# initial_schematic.net
KiCad netlist of a schematic drawn in EAGLE
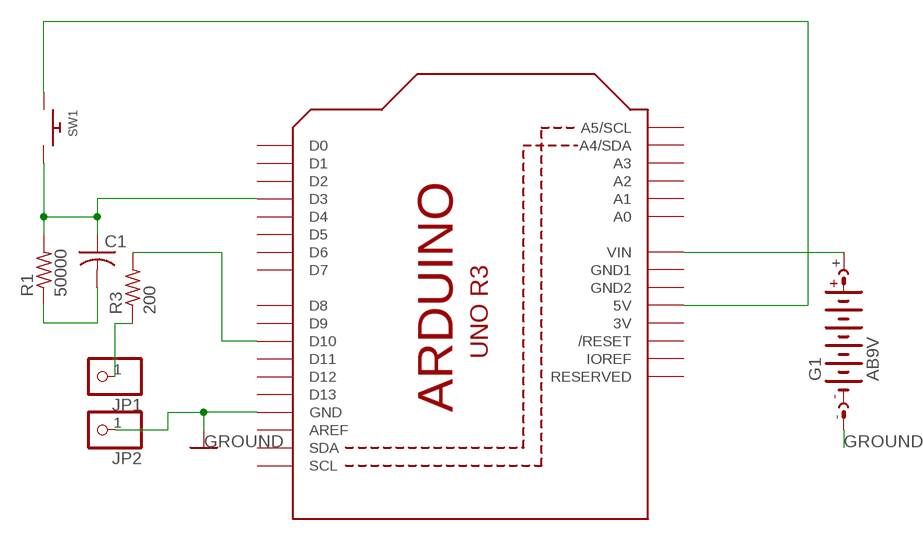
[diagram p0: schematic, sheet 1]

(export (version "E")
  (design (tool "Eeschema 10.0.6"))
  (components
    (comp (ref "C1")
      (value "C-USC0805")
      (footprint "eagle-import:C0805")
      (libsource (lib "eagle-import") (part "C-USC0805"))
    )
    (comp (ref "G1")
      (value "AB9V")
      (footprint "eagle-import:AB9V")
      (libsource (lib "eagle-import") (part "AB9V"))
    )
    (comp (ref "JP1")
      (value "PINHD-1X1")
      (footprint "eagle-import:1X01")
      (libsource (lib "eagle-import") (part "PINHD-1X1"))
    )
    (comp (ref "JP2")
      (value "PINHD-1X1")
      (footprint "eagle-import:1X01")
      (libsource (lib "eagle-import") (part "PINHD-1X1"))
    )
    (comp (ref "R1")
      (value "50000")
      (footprint "eagle-import:R0805W")
      (libsource (lib "eagle-import") (part "R-US_R0805W"))
    )
    (comp (ref "R3")
      (value "200")
      (footprint "eagle-import:R0805W")
      (libsource (lib "eagle-import") (part "R-US_R0805W"))
    )
    (comp (ref "SW1")
      (value "SWITCH_PUSHBUTTONC&K_KSS")
      (footprint "eagle-import:BTN_CK_KSS")
      (libsource (lib "eagle-import") (part "SWITCH_PUSHBUTTONC&K_KSS"))
    )
    (comp (ref "U1")
      (value "ARDUINOR3-DIMENSION")
      (footprint "eagle-import:ARDUINOR3")
      (libsource (lib "eagle-import") (part "ARDUINOR3-DIMENSION"))
    )
  )
  (nets
    (net (code "1") (name "/3V") (class "Default")
      (node (ref "U1") (pin "3V") (pinfunction "3V_3V") (pintype "power_in"))
    )
    (net (code "2") (name "/GND1") (class "Default")
      (node (ref "U1") (pin "GND1") (pinfunction "GND1_GND1") (pintype "power_in"))
    )
    (net (code "3") (name "/GND2") (class "Default")
      (node (ref "U1") (pin "GND2") (pinfunction "GND2_GND2") (pintype "power_in"))
    )
    (net (code "4") (name "GND") (class "Default")
      (node (ref "JP2") (pin "1") (pinfunction "1_1") (pintype "passive"))
      (node (ref "U1") (pin "GND") (pinfunction "GND_GND") (pintype "power_in"))
    )
    (net (code "5") (name "Net-(C1-Pad1)") (class "Default")
      (node (ref "C1") (pin "1") (pinfunction "1_1") (pintype "passive"))
      (node (ref "R1") (pin "2") (pinfunction "2_2") (pintype "passive"))
      (node (ref "SW1") (pin "P$2") (pinfunction "P$2_P$2") (pintype "passive"))
      (node (ref "U1") (pin "D3") (pinfunction "D3_D3") (pintype "bidirectional"))
    )
    (net (code "6") (name "Net-(C1-Pad2)") (class "Default")
      (node (ref "C1") (pin "2") (pinfunction "2_2") (pintype "passive"))
      (node (ref "R1") (pin "1") (pinfunction "1_1") (pintype "passive"))
    )
    (net (code "7") (name "Net-(G1-Pad+)") (class "Default")
      (node (ref "G1") (pin "+") (pinfunction "+_+") (pintype "passive"))
      (node (ref "U1") (pin "VIN") (pinfunction "VIN_VIN") (pintype "power_in"))
    )
    (net (code "8") (name "Net-(JP1-Pad1)") (class "Default")
      (node (ref "JP1") (pin "1") (pinfunction "1_1") (pintype "passive"))
      (node (ref "R3") (pin "1") (pinfunction "1_1") (pintype "passive"))
    )
    (net (code "9") (name "Net-(R3-Pad2)") (class "Default")
      (node (ref "R3") (pin "2") (pinfunction "2_2") (pintype "passive"))
      (node (ref "U1") (pin "D10") (pinfunction "D10_D10") (pintype "bidirectional"))
    )
    (net (code "10") (name "Net-(SW1-PadP$1)") (class "Default")
      (node (ref "SW1") (pin "P$1") (pinfunction "P$1_P$1") (pintype "passive"))
      (node (ref "U1") (pin "5V") (pinfunction "5V_5V") (pintype "power_in"))
    )
    (net (code "11") (name "unconnected-(G1-Pad-)") (class "Default")
      (node (ref "G1") (pin "-") (pinfunction "-_-") (pintype "passive"))
    )
    (net (code "12") (name "unconnected-(U1-A4{slash}SDA-PadA4)") (class "Default")
      (node (ref "U1") (pin "A4") (pinfunction "A4/SDA_A4") (pintype "bidirectional"))
    )
    (net (code "13") (name "unconnected-(U1-A5{slash}SCL-PadA5)") (class "Default")
      (node (ref "U1") (pin "A5") (pinfunction "A5/SCL_A5") (pintype "bidirectional"))
    )
    (net (code "14") (name "unconnected-(U1-PadA0)") (class "Default")
      (node (ref "U1") (pin "A0") (pinfunction "A0_A0") (pintype "bidirectional"))
    )
    (net (code "15") (name "unconnected-(U1-PadA1)") (class "Default")
      (node (ref "U1") (pin "A1") (pinfunction "A1_A1") (pintype "bidirectional"))
    )
    (net (code "16") (name "unconnected-(U1-PadA2)") (class "Default")
      (node (ref "U1") (pin "A2") (pinfunction "A2_A2") (pintype "bidirectional"))
    )
    (net (code "17") (name "unconnected-(U1-PadA3)") (class "Default")
      (node (ref "U1") (pin "A3") (pinfunction "A3_A3") (pintype "bidirectional"))
    )
    (net (code "18") (name "unconnected-(U1-PadAREF)") (class "Default")
      (node (ref "U1") (pin "AREF") (pinfunction "AREF_AREF") (pintype "bidirectional"))
    )
    (net (code "19") (name "unconnected-(U1-PadD0)") (class "Default")
      (node (ref "U1") (pin "D0") (pinfunction "D0_D0") (pintype "bidirectional"))
    )
    (net (code "20") (name "unconnected-(U1-PadD1)") (class "Default")
      (node (ref "U1") (pin "D1") (pinfunction "D1_D1") (pintype "bidirectional"))
    )
    (net (code "21") (name "unconnected-(U1-PadD2)") (class "Default")
      (node (ref "U1") (pin "D2") (pinfunction "D2_D2") (pintype "bidirectional"))
    )
    (net (code "22") (name "unconnected-(U1-PadD4)") (class "Default")
      (node (ref "U1") (pin "D4") (pinfunction "D4_D4") (pintype "bidirectional"))
    )
    (net (code "23") (name "unconnected-(U1-PadD5)") (class "Default")
      (node (ref "U1") (pin "D5") (pinfunction "D5_D5") (pintype "bidirectional"))
    )
    (net (code "24") (name "unconnected-(U1-PadD6)") (class "Default")
      (node (ref "U1") (pin "D6") (pinfunction "D6_D6") (pintype "bidirectional"))
    )
    (net (code "25") (name "unconnected-(U1-PadD7)") (class "Default")
      (node (ref "U1") (pin "D7") (pinfunction "D7_D7") (pintype "bidirectional"))
    )
    (net (code "26") (name "unconnected-(U1-PadD8)") (class "Default")
      (node (ref "U1") (pin "D8") (pinfunction "D8_D8") (pintype "bidirectional"))
    )
    (net (code "27") (name "unconnected-(U1-PadD9)") (class "Default")
      (node (ref "U1") (pin "D9") (pinfunction "D9_D9") (pintype "bidirectional"))
    )
    (net (code "28") (name "unconnected-(U1-PadD11)") (class "Default")
      (node (ref "U1") (pin "D11") (pinfunction "D11_D11") (pintype "bidirectional"))
    )
    (net (code "29") (name "unconnected-(U1-PadD12)") (class "Default")
      (node (ref "U1") (pin "D12") (pinfunction "D12_D12") (pintype "bidirectional"))
    )
    (net (code "30") (name "unconnected-(U1-PadD13)") (class "Default")
      (node (ref "U1") (pin "D13") (pinfunction "D13_D13") (pintype "bidirectional"))
    )
    (net (code "31") (name "unconnected-(U1-PadIOREF)") (class "Default")
      (node (ref "U1") (pin "IOREF") (pinfunction "IOREF_IOREF") (pintype "output"))
    )
    (net (code "32") (name "unconnected-(U1-PadRESERVED)") (class "Default")
      (node (ref "U1") (pin "RESERVED") (pinfunction "RESERVED_RESERVED") (pintype "no_connect"))
    )
    (net (code "33") (name "unconnected-(U1-PadSCL)") (class "Default")
      (node (ref "U1") (pin "SCL") (pinfunction "SCL_SCL") (pintype "bidirectional"))
    )
    (net (code "34") (name "unconnected-(U1-PadSDA)") (class "Default")
      (node (ref "U1") (pin "SDA") (pinfunction "SDA_SDA") (pintype "bidirectional"))
    )
    (net (code "35") (name "unconnected-(U1-{slash}RESET-PadRESET)") (class "Default")
      (node (ref "U1") (pin "RESET") (pinfunction "/RESET_RESET") (pintype "bidirectional"))
    )
  )
)
